# TempSensorBuddyV1.net
KiCad netlist of a schematic drawn in EAGLE
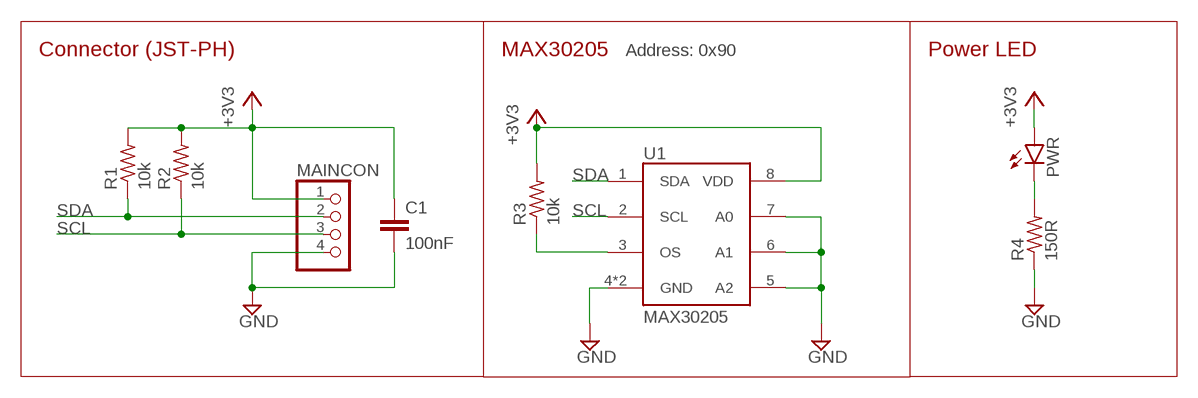
[diagram p0: schematic, sheet 1]

(export (version "E")
  (design (tool "Eeschema 10.0.6"))
  (components
    (comp (ref "C1")
      (value "100nF")
      (footprint "eagle-import:C0603")
      (libsource (lib "eagle-import") (part "C-EUC0603"))
    )
    (comp (ref "MAINCON")
      (value "PINHD-1X4M")
      (footprint "eagle-import:1X04M")
      (libsource (lib "eagle-import") (part "PINHD-1X4M"))
    )
    (comp (ref "PWR")
      (value "LEDCHIPLED_0805")
      (footprint "eagle-import:CHIPLED_0805")
      (libsource (lib "eagle-import") (part "LEDCHIPLED_0805"))
    )
    (comp (ref "R1")
      (value "10k")
      (footprint "eagle-import:R0603")
      (libsource (lib "eagle-import") (part "R-US_R0603"))
    )
    (comp (ref "R2")
      (value "10k")
      (footprint "eagle-import:R0603")
      (libsource (lib "eagle-import") (part "R-US_R0603"))
    )
    (comp (ref "R3")
      (value "10k")
      (footprint "eagle-import:R0603")
      (libsource (lib "eagle-import") (part "R-US_R0603"))
    )
    (comp (ref "R4")
      (value "150R")
      (footprint "eagle-import:R0603")
      (libsource (lib "eagle-import") (part "R-US_R0603"))
    )
    (comp (ref "U1")
      (value "MAX30205")
      (footprint "eagle-import:DFN-8")
      (libsource (lib "eagle-import") (part "MAX30205"))
    )
  )
  (nets
    (net (code "1") (name "+3V3") (class "Default")
      (node (ref "C1") (pin "1") (pinfunction "1_1") (pintype "passive"))
      (node (ref "MAINCON") (pin "1") (pinfunction "1_1") (pintype "passive"))
      (node (ref "PWR") (pin "A") (pinfunction "A_A") (pintype "passive"))
      (node (ref "R1") (pin "2") (pinfunction "2_2") (pintype "passive"))
      (node (ref "R2") (pin "2") (pinfunction "2_2") (pintype "passive"))
      (node (ref "R3") (pin "2") (pinfunction "2_2") (pintype "passive"))
      (node (ref "U1") (pin "8") (pinfunction "VDD_8") (pintype "bidirectional"))
    )
    (net (code "2") (name "/SCL") (class "Default")
      (node (ref "MAINCON") (pin "3") (pinfunction "3_3") (pintype "passive"))
      (node (ref "R2") (pin "1") (pinfunction "1_1") (pintype "passive"))
      (node (ref "U1") (pin "2") (pinfunction "SCL_2") (pintype "bidirectional"))
    )
    (net (code "3") (name "/SDA") (class "Default")
      (node (ref "MAINCON") (pin "2") (pinfunction "2_2") (pintype "passive"))
      (node (ref "R1") (pin "1") (pinfunction "1_1") (pintype "passive"))
      (node (ref "U1") (pin "1") (pinfunction "SDA_1") (pintype "bidirectional"))
    )
    (net (code "4") (name "GND") (class "Default")
      (node (ref "C1") (pin "2") (pinfunction "2_2") (pintype "passive"))
      (node (ref "MAINCON") (pin "4") (pinfunction "4_4") (pintype "passive"))
      (node (ref "R4") (pin "1") (pinfunction "1_1") (pintype "passive"))
      (node (ref "U1") (pin "4") (pinfunction "GND_4") (pintype "bidirectional"))
      (node (ref "U1") (pin "5") (pinfunction "A2_5") (pintype "bidirectional"))
      (node (ref "U1") (pin "6") (pinfunction "A1_6") (pintype "bidirectional"))
      (node (ref "U1") (pin "7") (pinfunction "A0_7") (pintype "bidirectional"))
      (node (ref "U1") (pin "9") (pinfunction "GND_9") (pintype "bidirectional"))
    )
    (net (code "5") (name "Net-(PWR-PadC)") (class "Default")
      (node (ref "PWR") (pin "C") (pinfunction "C_C") (pintype "passive"))
      (node (ref "R4") (pin "2") (pinfunction "2_2") (pintype "passive"))
    )
    (net (code "6") (name "Net-(U1-OS)") (class "Default")
      (node (ref "R3") (pin "1") (pinfunction "1_1") (pintype "passive"))
      (node (ref "U1") (pin "3") (pinfunction "OS_3") (pintype "bidirectional"))
    )
  )
)
